# DSP_Lab_SS21_Keyboard_V2.net
KiCad netlist of a schematic drawn in EAGLE
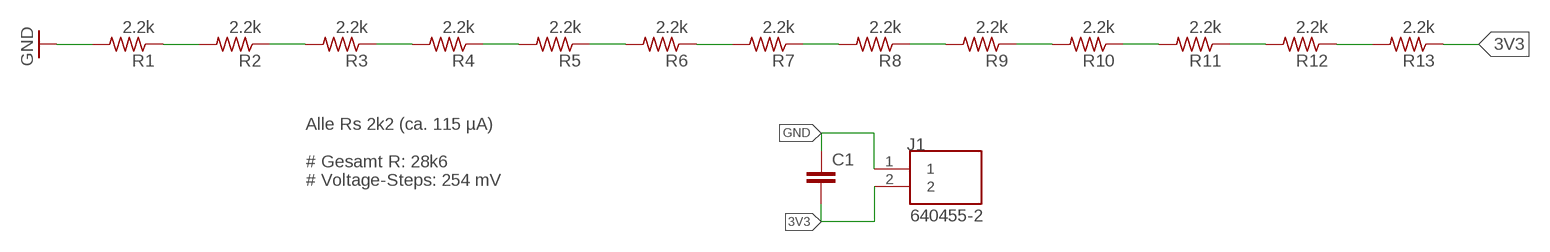
[diagram p0: schematic, sheet 1]

(export (version "E")
  (design (tool "Eeschema 10.0.6"))
  (components
    (comp (ref "C1")
      (value "C-EUC0603")
      (footprint "eagle-import:C0603")
      (libsource (lib "eagle-import") (part "C-EUC0603"))
    )
    (comp (ref "J1")
      (value "640455-2")
      (footprint "eagle-import:TE_640455-2")
      (fields (field (name "MF") "TE Connectivity"))
      (libsource (lib "eagle-import") (part "640455-2"))
    )
    (comp (ref "R1")
      (value "2.2k")
      (footprint "eagle-import:R0603")
      (libsource (lib "eagle-import") (part "R-US_R0603"))
    )
    (comp (ref "R2")
      (value "2.2k")
      (footprint "eagle-import:R0603")
      (libsource (lib "eagle-import") (part "R-US_R0603"))
    )
    (comp (ref "R3")
      (value "2.2k")
      (footprint "eagle-import:R0603")
      (libsource (lib "eagle-import") (part "R-US_R0603"))
    )
    (comp (ref "R4")
      (value "2.2k")
      (footprint "eagle-import:R0603")
      (libsource (lib "eagle-import") (part "R-US_R0603"))
    )
    (comp (ref "R5")
      (value "2.2k")
      (footprint "eagle-import:R0603")
      (libsource (lib "eagle-import") (part "R-US_R0603"))
    )
    (comp (ref "R6")
      (value "2.2k")
      (footprint "eagle-import:R0603")
      (libsource (lib "eagle-import") (part "R-US_R0603"))
    )
    (comp (ref "R7")
      (value "2.2k")
      (footprint "eagle-import:R0603")
      (libsource (lib "eagle-import") (part "R-US_R0603"))
    )
    (comp (ref "R8")
      (value "2.2k")
      (footprint "eagle-import:R0603")
      (libsource (lib "eagle-import") (part "R-US_R0603"))
    )
    (comp (ref "R9")
      (value "2.2k")
      (footprint "eagle-import:R0603")
      (libsource (lib "eagle-import") (part "R-US_R0603"))
    )
    (comp (ref "R10")
      (value "2.2k")
      (footprint "eagle-import:R0603")
      (libsource (lib "eagle-import") (part "R-US_R0603"))
    )
    (comp (ref "R11")
      (value "2.2k")
      (footprint "eagle-import:R0603")
      (libsource (lib "eagle-import") (part "R-US_R0603"))
    )
    (comp (ref "R12")
      (value "2.2k")
      (footprint "eagle-import:R0603")
      (libsource (lib "eagle-import") (part "R-US_R0603"))
    )
    (comp (ref "R13")
      (value "2.2k")
      (footprint "eagle-import:R0603")
      (libsource (lib "eagle-import") (part "R-US_R0603"))
    )
  )
  (nets
    (net (code "1") (name "3V3") (class "Default")
      (node (ref "C1") (pin "2") (pinfunction "2_2") (pintype "passive"))
      (node (ref "J1") (pin "2") (pinfunction "2_2") (pintype "passive"))
      (node (ref "R13") (pin "1") (pinfunction "1_1") (pintype "passive"))
    )
    (net (code "2") (name "GND") (class "Default")
      (node (ref "C1") (pin "1") (pinfunction "1_1") (pintype "passive"))
      (node (ref "J1") (pin "1") (pinfunction "1_1") (pintype "passive"))
      (node (ref "R1") (pin "2") (pinfunction "2_2") (pintype "passive"))
    )
    (net (code "3") (name "Net-(R1-Pad1)") (class "Default")
      (node (ref "R1") (pin "1") (pinfunction "1_1") (pintype "passive"))
      (node (ref "R2") (pin "2") (pinfunction "2_2") (pintype "passive"))
    )
    (net (code "4") (name "Net-(R2-Pad1)") (class "Default")
      (node (ref "R2") (pin "1") (pinfunction "1_1") (pintype "passive"))
      (node (ref "R3") (pin "2") (pinfunction "2_2") (pintype "passive"))
    )
    (net (code "5") (name "Net-(R3-Pad1)") (class "Default")
      (node (ref "R3") (pin "1") (pinfunction "1_1") (pintype "passive"))
      (node (ref "R4") (pin "2") (pinfunction "2_2") (pintype "passive"))
    )
    (net (code "6") (name "Net-(R4-Pad1)") (class "Default")
      (node (ref "R4") (pin "1") (pinfunction "1_1") (pintype "passive"))
      (node (ref "R5") (pin "2") (pinfunction "2_2") (pintype "passive"))
    )
    (net (code "7") (name "Net-(R5-Pad1)") (class "Default")
      (node (ref "R5") (pin "1") (pinfunction "1_1") (pintype "passive"))
      (node (ref "R6") (pin "2") (pinfunction "2_2") (pintype "passive"))
    )
    (net (code "8") (name "Net-(R6-Pad1)") (class "Default")
      (node (ref "R6") (pin "1") (pinfunction "1_1") (pintype "passive"))
      (node (ref "R7") (pin "2") (pinfunction "2_2") (pintype "passive"))
    )
    (net (code "9") (name "Net-(R7-Pad1)") (class "Default")
      (node (ref "R7") (pin "1") (pinfunction "1_1") (pintype "passive"))
      (node (ref "R8") (pin "2") (pinfunction "2_2") (pintype "passive"))
    )
    (net (code "10") (name "Net-(R8-Pad1)") (class "Default")
      (node (ref "R8") (pin "1") (pinfunction "1_1") (pintype "passive"))
      (node (ref "R9") (pin "2") (pinfunction "2_2") (pintype "passive"))
    )
    (net (code "11") (name "Net-(R10-Pad1)") (class "Default")
      (node (ref "R10") (pin "1") (pinfunction "1_1") (pintype "passive"))
      (node (ref "R11") (pin "2") (pinfunction "2_2") (pintype "passive"))
    )
    (net (code "12") (name "Net-(R10-Pad2)") (class "Default")
      (node (ref "R10") (pin "2") (pinfunction "2_2") (pintype "passive"))
      (node (ref "R9") (pin "1") (pinfunction "1_1") (pintype "passive"))
    )
    (net (code "13") (name "Net-(R11-Pad1)") (class "Default")
      (node (ref "R11") (pin "1") (pinfunction "1_1") (pintype "passive"))
      (node (ref "R12") (pin "2") (pinfunction "2_2") (pintype "passive"))
    )
    (net (code "14") (name "Net-(R12-Pad1)") (class "Default")
      (node (ref "R12") (pin "1") (pinfunction "1_1") (pintype "passive"))
      (node (ref "R13") (pin "2") (pinfunction "2_2") (pintype "passive"))
    )
  )
)
